# F1C100s.net
KiCad netlist of a schematic drawn in Altium Designer
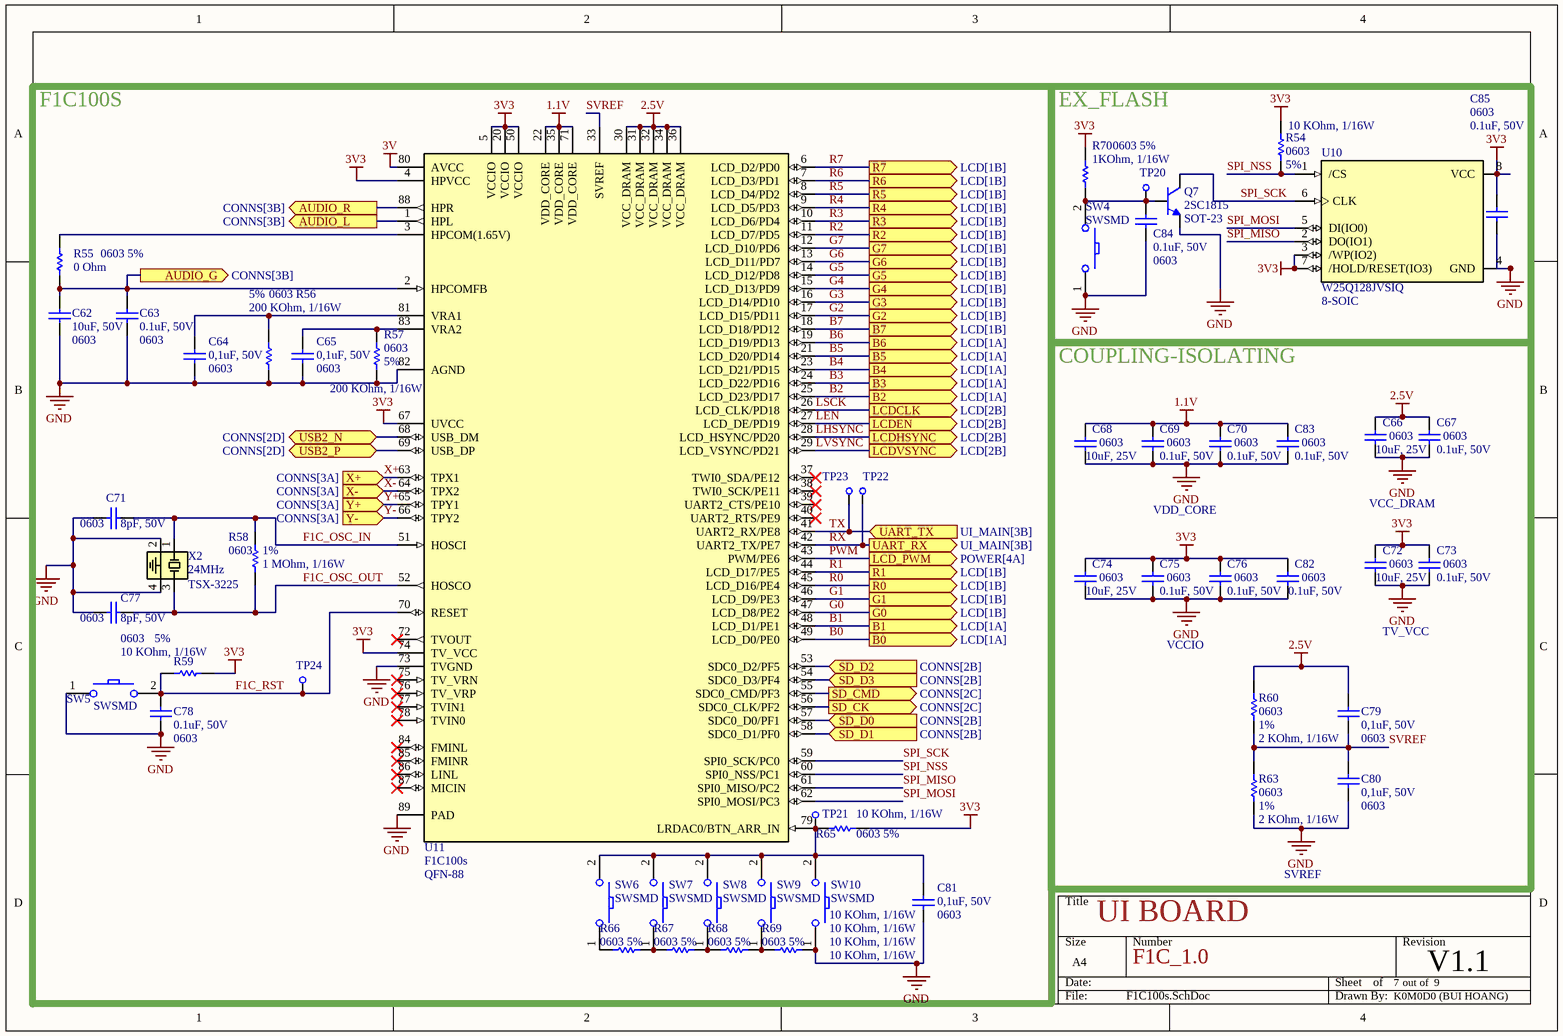
[diagram p0: F1C100s.SchDoc]

(export (version "E")
  (design (tool "Eeschema 10.0.6"))
  (components
    (comp (ref "C62")
      (value "10uF, 50V")
      (footprint "C_0603")
      (description "CAP_0603")
      (fields (field (name "PACKAGE") "0603"))
      (libsource (lib "DisplayLib") (part "CAP_0603"))
    )
    (comp (ref "C63")
      (value "0.1uF, 50V")
      (footprint "C_0603")
      (description "CAP_0603")
      (fields (field (name "PACKAGE") "0603"))
      (libsource (lib "DisplayLib") (part "CAP_0603"))
    )
    (comp (ref "C64")
      (value "0,1uF, 50V")
      (footprint "C_0603")
      (description "CAP_0603")
      (fields (field (name "PACKAGE") "0603"))
      (libsource (lib "DisplayLib") (part "CAP_0603"))
    )
    (comp (ref "C65")
      (value "0,1uF, 50V")
      (footprint "C_0603")
      (description "CAP_0603")
      (fields (field (name "PACKAGE") "0603"))
      (libsource (lib "DisplayLib") (part "CAP_0603"))
    )
    (comp (ref "C66")
      (value "10uF, 25V")
      (footprint "C_0603")
      (description "CAP_0603")
      (fields (field (name "PACKAGE") "0603"))
      (libsource (lib "DisplayLib") (part "CAP_0603"))
    )
    (comp (ref "C67")
      (value "0.1uF, 50V")
      (footprint "C_0603")
      (description "CAP_0603")
      (fields (field (name "PACKAGE") "0603"))
      (libsource (lib "DisplayLib") (part "CAP_0603"))
    )
    (comp (ref "C68")
      (value "10uF, 25V")
      (footprint "C_0603")
      (description "CAP_0603")
      (fields (field (name "PACKAGE") "0603"))
      (libsource (lib "DisplayLib") (part "CAP_0603"))
    )
    (comp (ref "C69")
      (value "0.1uF, 50V")
      (footprint "C_0603")
      (description "CAP_0603")
      (fields (field (name "PACKAGE") "0603"))
      (libsource (lib "DisplayLib") (part "CAP_0603"))
    )
    (comp (ref "C70")
      (value "0.1uF, 50V")
      (footprint "C_0603")
      (description "CAP_0603")
      (fields (field (name "PACKAGE") "0603"))
      (libsource (lib "DisplayLib") (part "CAP_0603"))
    )
    (comp (ref "C71")
      (value "8pF, 50V")
      (footprint "C_0603")
      (description "CAP_0603")
      (fields (field (name "PACKAGE") "0603"))
      (libsource (lib "DisplayLib") (part "CAP_0603"))
    )
    (comp (ref "C72")
      (value "10uF, 25V")
      (footprint "C_0603")
      (description "CAP_0603")
      (fields (field (name "PACKAGE") "0603"))
      (libsource (lib "DisplayLib") (part "CAP_0603"))
    )
    (comp (ref "C73")
      (value "0.1uF, 50V")
      (footprint "C_0603")
      (description "CAP_0603")
      (fields (field (name "PACKAGE") "0603"))
      (libsource (lib "DisplayLib") (part "CAP_0603"))
    )
    (comp (ref "C74")
      (value "10uF, 25V")
      (footprint "C_0603")
      (description "CAP_0603")
      (fields (field (name "PACKAGE") "0603"))
      (libsource (lib "DisplayLib") (part "CAP_0603"))
    )
    (comp (ref "C75")
      (value "0.1uF, 50V")
      (footprint "C_0603")
      (description "CAP_0603")
      (fields (field (name "PACKAGE") "0603"))
      (libsource (lib "DisplayLib") (part "CAP_0603"))
    )
    (comp (ref "C76")
      (value "0.1uF, 50V")
      (footprint "C_0603")
      (description "CAP_0603")
      (fields (field (name "PACKAGE") "0603"))
      (libsource (lib "DisplayLib") (part "CAP_0603"))
    )
    (comp (ref "C77")
      (value "8pF, 50V")
      (footprint "C_0603")
      (description "CAP_0603")
      (fields (field (name "PACKAGE") "0603"))
      (libsource (lib "DisplayLib") (part "CAP_0603"))
    )
    (comp (ref "C78")
      (value "0.1uF, 50V")
      (footprint "C_0603")
      (description "CAP_0603")
      (fields (field (name "PACKAGE") "0603"))
      (libsource (lib "DisplayLib") (part "CAP_0603"))
    )
    (comp (ref "C79")
      (value "0,1uF, 50V")
      (footprint "C_0603")
      (description "CAP_0603")
      (fields (field (name "PACKAGE") "0603"))
      (libsource (lib "DisplayLib") (part "CAP_0603"))
    )
    (comp (ref "C80")
      (value "0,1uF, 50V")
      (footprint "C_0603")
      (description "CAP_0603")
      (fields (field (name "PACKAGE") "0603"))
      (libsource (lib "DisplayLib") (part "CAP_0603"))
    )
    (comp (ref "C81")
      (value "0,1uF, 50V")
      (footprint "C_0603")
      (description "CAP_0603")
      (fields (field (name "PACKAGE") "0603"))
      (libsource (lib "DisplayLib") (part "CAP_0603"))
    )
    (comp (ref "C82")
      (value "0.1uF, 50V")
      (footprint "C_0603")
      (description "CAP_0603")
      (fields (field (name "PACKAGE") "0603"))
      (libsource (lib "DisplayLib") (part "CAP_0603"))
    )
    (comp (ref "C83")
      (value "0.1uF, 50V")
      (footprint "C_0603")
      (description "CAP_0603")
      (fields (field (name "PACKAGE") "0603"))
      (libsource (lib "DisplayLib") (part "CAP_0603"))
    )
    (comp (ref "C84")
      (value "0.1uF, 50V")
      (footprint "C_0603")
      (description "CAP_0603")
      (fields (field (name "PACKAGE") "0603"))
      (libsource (lib "DisplayLib") (part "CAP_0603"))
    )
    (comp (ref "C85")
      (value "0.1uF, 50V")
      (footprint "C_0603")
      (description "CAP_0603")
      (fields (field (name "PACKAGE") "0603"))
      (libsource (lib "DisplayLib") (part "CAP_0603"))
    )
    (comp (ref "Q7")
      (value "2SC1815")
      (footprint "PKG_SOT-23")
      (description "HF Transistor NPN")
      (fields (field (name "PACKAGE") "SOT-23"))
      (libsource (lib "DisplayLib") (part "2SC1815"))
    )
    (comp (ref "R54")
      (value "10 KOhm, 1/16W")
      (footprint "R_0603")
      (description "RES_0603")
      (fields (field (name "PACKAGE") "0603") (field (name "ACC") "5%"))
      (libsource (lib "DisplayLib") (part "RES_0603"))
    )
    (comp (ref "R55")
      (value "0 Ohm")
      (footprint "R_0603")
      (description "RES_0603")
      (fields (field (name "PACKAGE") "0603") (field (name "ACC") "5%"))
      (libsource (lib "DisplayLib") (part "RES_0603"))
    )
    (comp (ref "R56")
      (value "200 KOhm, 1/16W")
      (footprint "R_0603")
      (description "RES_0603")
      (fields (field (name "PACKAGE") "0603") (field (name "ACC") "5%"))
      (libsource (lib "DisplayLib") (part "RES_0603"))
    )
    (comp (ref "R57")
      (value "200 KOhm, 1/16W")
      (footprint "R_0603")
      (description "RES_0603")
      (fields (field (name "PACKAGE") "0603") (field (name "ACC") "5%"))
      (libsource (lib "DisplayLib") (part "RES_0603"))
    )
    (comp (ref "R58")
      (value "1 MOhm, 1/16W")
      (footprint "R_0603")
      (description "RES_0603")
      (fields (field (name "PACKAGE") "0603") (field (name "ACC") "1%"))
      (libsource (lib "DisplayLib") (part "RES_0603"))
    )
    (comp (ref "R59")
      (value "10 KOhm, 1/16W")
      (footprint "R_0603")
      (description "RES_0603")
      (fields (field (name "PACKAGE") "0603") (field (name "ACC") "5%"))
      (libsource (lib "DisplayLib") (part "RES_0603"))
    )
    (comp (ref "R60")
      (value "2 KOhm, 1/16W")
      (footprint "R_0603")
      (description "RES_0603")
      (fields (field (name "PACKAGE") "0603") (field (name "ACC") "1%"))
      (libsource (lib "DisplayLib") (part "RES_0603"))
    )
    (comp (ref "R63")
      (value "2 KOhm, 1/16W")
      (footprint "R_0603")
      (description "RES_0603")
      (fields (field (name "PACKAGE") "0603") (field (name "ACC") "1%"))
      (libsource (lib "DisplayLib") (part "RES_0603"))
    )
    (comp (ref "R65")
      (value "10 KOhm, 1/16W")
      (footprint "R_0603")
      (description "RES_0603")
      (fields (field (name "PACKAGE") "0603") (field (name "ACC") "5%"))
      (libsource (lib "DisplayLib") (part "RES_0603"))
    )
    (comp (ref "R66")
      (value "10 KOhm, 1/16W")
      (footprint "R_0603")
      (description "RES_0603")
      (fields (field (name "PACKAGE") "0603") (field (name "ACC") "5%"))
      (libsource (lib "DisplayLib") (part "RES_0603"))
    )
    (comp (ref "R67")
      (value "10 KOhm, 1/16W")
      (footprint "R_0603")
      (description "RES_0603")
      (fields (field (name "PACKAGE") "0603") (field (name "ACC") "5%"))
      (libsource (lib "DisplayLib") (part "RES_0603"))
    )
    (comp (ref "R68")
      (value "10 KOhm, 1/16W")
      (footprint "R_0603")
      (description "RES_0603")
      (fields (field (name "PACKAGE") "0603") (field (name "ACC") "5%"))
      (libsource (lib "DisplayLib") (part "RES_0603"))
    )
    (comp (ref "R69")
      (value "10 KOhm, 1/16W")
      (footprint "R_0603")
      (description "RES_0603")
      (fields (field (name "PACKAGE") "0603") (field (name "ACC") "5%"))
      (libsource (lib "DisplayLib") (part "RES_0603"))
    )
    (comp (ref "R70")
      (value "1KOhm, 1/16W")
      (footprint "R_0603")
      (description "RES_0603")
      (fields (field (name "PACKAGE") "0603") (field (name "ACC") "5%"))
      (libsource (lib "DisplayLib") (part "RES_0603"))
    )
    (comp (ref "SW4")
      (value "SWSMD")
      (footprint "SW_SMD_NOGND")
      (description "SW_SMD")
      (libsource (lib "") (part "SWSMD_NOGND_1"))
    )
    (comp (ref "SW5")
      (value "SWSMD")
      (footprint "SW_SMD_NOGND")
      (description "SW_SMD")
      (libsource (lib "DisplayLib") (part "SWSMD_NOGND"))
    )
    (comp (ref "SW6")
      (value "SWSMD")
      (footprint "SW_SMD_NOGND")
      (description "SW_SMD")
      (libsource (lib "") (part "SWSMD_NOGND_1"))
    )
    (comp (ref "SW7")
      (value "SWSMD")
      (footprint "SW_SMD_NOGND")
      (description "SW_SMD")
      (libsource (lib "") (part "SWSMD_NOGND_1"))
    )
    (comp (ref "SW8")
      (value "SWSMD")
      (footprint "SW_SMD_NOGND")
      (description "SW_SMD")
      (libsource (lib "") (part "SWSMD_NOGND_1"))
    )
    (comp (ref "SW9")
      (value "SWSMD")
      (footprint "SW_SMD_NOGND")
      (description "SW_SMD")
      (libsource (lib "") (part "SWSMD_NOGND_1"))
    )
    (comp (ref "SW10")
      (value "SWSMD")
      (footprint "SW_SMD_NOGND")
      (description "SW_SMD")
      (libsource (lib "") (part "SWSMD_NOGND_1"))
    )
    (comp (ref "TP20")
      (value "TESTPT")
      (footprint "TESTPT")
      (description "Test point")
      (libsource (lib "DisplayLib") (part "TESTPT"))
    )
    (comp (ref "TP21")
      (value "TESTPT")
      (footprint "TESTPT")
      (description "Test point")
      (libsource (lib "DisplayLib") (part "TESTPT"))
    )
    (comp (ref "TP22")
      (value "TESTPT")
      (footprint "TESTPT")
      (description "Test point")
      (libsource (lib "DisplayLib") (part "TESTPT"))
    )
    (comp (ref "TP23")
      (value "TESTPT")
      (footprint "TESTPT")
      (description "Test point")
      (libsource (lib "DisplayLib") (part "TESTPT"))
    )
    (comp (ref "TP24")
      (value "TESTPT")
      (footprint "TESTPT")
      (description "Test point")
      (libsource (lib "DisplayLib") (part "TESTPT"))
    )
    (comp (ref "U10")
      (value "W25Q128JVSIQ")
      (footprint "PKG_8-SOIC")
      (description "FLASH - NOR Memory IC 128Mb (16M x 8) SPI - Quad I/O, QPI, DTR 133 MHz 8-SOIC")
      (fields (field (name "PACKAGE") "8-SOIC"))
      (libsource (lib "DisplayLib") (part "W25Q128JVSIQ"))
    )
    (comp (ref "U11")
      (value "F1C100s")
      (footprint "PKG_QFN-88")
      (fields (field (name "PACKAGE") "QFN-88"))
      (libsource (lib "DisplayLib") (part "F1C100s"))
    )
    (comp (ref "X2")
      (value "24MHz")
      (footprint "PKG_TSX-3225")
      (description "Crystal, 24 MHz, -30 to 85 degC, 3.2 x 2.5 x 0.9 mm SMD")
      (fields (field (name "PACKAGE") "TSX-3225"))
      (libsource (lib "DisplayLib") (part "XTAL"))
    )
  )
  (nets
    (net (code "1") (name "/AUDIO_G") (class "Default")
      (node (ref "C62") (pin "2") (pinfunction "2_2") (pintype "passive"))
      (node (ref "C63") (pin "2") (pinfunction "2_2") (pintype "passive"))
      (node (ref "R55") (pin "1") (pinfunction "1_1") (pintype "passive"))
      (node (ref "U11") (pin "2") (pinfunction "HPCOMFB_2") (pintype "input"))
    )
    (net (code "2") (name "/AUDIO_L") (class "Default")
      (node (ref "U11") (pin "1") (pinfunction "HPL_1") (pintype "output"))
    )
    (net (code "3") (name "/AUDIO_R") (class "Default")
      (node (ref "U11") (pin "88") (pinfunction "HPR_88") (pintype "output"))
    )
    (net (code "4") (name "/B0") (class "Default")
      (node (ref "U11") (pin "49") (pinfunction "LCD_D0/PE0_49") (pintype "bidirectional"))
    )
    (net (code "5") (name "/B1") (class "Default")
      (node (ref "U11") (pin "48") (pinfunction "LCD_D1/PE1_48") (pintype "bidirectional"))
    )
    (net (code "6") (name "/B2") (class "Default")
      (node (ref "U11") (pin "25") (pinfunction "LCD_D23/PD17_25") (pintype "bidirectional"))
    )
    (net (code "7") (name "/B3") (class "Default")
      (node (ref "U11") (pin "24") (pinfunction "LCD_D22/PD16_24") (pintype "bidirectional"))
    )
    (net (code "8") (name "/B4") (class "Default")
      (node (ref "U11") (pin "23") (pinfunction "LCD_D21/PD15_23") (pintype "bidirectional"))
    )
    (net (code "9") (name "/B5") (class "Default")
      (node (ref "U11") (pin "21") (pinfunction "LCD_D20/PD14_21") (pintype "bidirectional"))
    )
    (net (code "10") (name "/B6") (class "Default")
      (node (ref "U11") (pin "19") (pinfunction "LCD_D19/PD13_19") (pintype "bidirectional"))
    )
    (net (code "11") (name "/B7") (class "Default")
      (node (ref "U11") (pin "18") (pinfunction "LCD_D18/PD12_18") (pintype "bidirectional"))
    )
    (net (code "12") (name "/F1C_OSC_IN") (class "Default")
      (node (ref "C71") (pin "2") (pinfunction "2_2") (pintype "passive"))
      (node (ref "R58") (pin "2") (pinfunction "2_2") (pintype "passive"))
      (node (ref "U11") (pin "51") (pinfunction "HOSCI_51") (pintype "input"))
      (node (ref "X2") (pin "1") (pinfunction "1_1") (pintype "passive"))
    )
    (net (code "13") (name "/F1C_OSC_OUT") (class "Default")
      (node (ref "C77") (pin "2") (pinfunction "2_2") (pintype "passive"))
      (node (ref "R58") (pin "1") (pinfunction "1_1") (pintype "passive"))
      (node (ref "U11") (pin "52") (pinfunction "HOSCO_52") (pintype "output"))
      (node (ref "X2") (pin "3") (pinfunction "3_3") (pintype "passive"))
    )
    (net (code "14") (name "/F1C_RST") (class "Default")
      (node (ref "C78") (pin "2") (pinfunction "2_2") (pintype "passive"))
      (node (ref "R59") (pin "1") (pinfunction "1_1") (pintype "passive"))
      (node (ref "SW5") (pin "2") (pinfunction "2_2") (pintype "passive"))
      (node (ref "TP24") (pin "1") (pinfunction "1_1") (pintype "passive"))
      (node (ref "U11") (pin "70") (pinfunction "RESET_70") (pintype "bidirectional"))
    )
    (net (code "15") (name "/G0") (class "Default")
      (node (ref "U11") (pin "47") (pinfunction "LCD_D8/PE2_47") (pintype "bidirectional"))
    )
    (net (code "16") (name "/G1") (class "Default")
      (node (ref "U11") (pin "46") (pinfunction "LCD_D9/PE3_46") (pintype "bidirectional"))
    )
    (net (code "17") (name "/G2") (class "Default")
      (node (ref "U11") (pin "17") (pinfunction "LCD_D15/PD11_17") (pintype "bidirectional"))
    )
    (net (code "18") (name "/G3") (class "Default")
      (node (ref "U11") (pin "16") (pinfunction "LCD_D14/PD10_16") (pintype "bidirectional"))
    )
    (net (code "19") (name "/G4") (class "Default")
      (node (ref "U11") (pin "15") (pinfunction "LCD_D13/PD9_15") (pintype "bidirectional"))
    )
    (net (code "20") (name "/G5") (class "Default")
      (node (ref "U11") (pin "14") (pinfunction "LCD_D12/PD8_14") (pintype "bidirectional"))
    )
    (net (code "21") (name "/G6") (class "Default")
      (node (ref "U11") (pin "13") (pinfunction "LCD_D11/PD7_13") (pintype "bidirectional"))
    )
    (net (code "22") (name "/G7") (class "Default")
      (node (ref "U11") (pin "12") (pinfunction "LCD_D10/PD6_12") (pintype "bidirectional"))
    )
    (net (code "23") (name "/LEN") (class "Default")
      (node (ref "U11") (pin "27") (pinfunction "LCD_DE/PD19_27") (pintype "bidirectional"))
    )
    (net (code "24") (name "/LHSYNC") (class "Default")
      (node (ref "U11") (pin "28") (pinfunction "LCD_HSYNC/PD20_28") (pintype "bidirectional"))
    )
    (net (code "25") (name "/LSCK") (class "Default")
      (node (ref "U11") (pin "26") (pinfunction "LCD_CLK/PD18_26") (pintype "bidirectional"))
    )
    (net (code "26") (name "/LVSYNC") (class "Default")
      (node (ref "U11") (pin "29") (pinfunction "LCD_VSYNC/PD21_29") (pintype "bidirectional"))
    )
    (net (code "27") (name "/PWM") (class "Default")
      (node (ref "U11") (pin "43") (pinfunction "PWM/PE6_43") (pintype "bidirectional"))
    )
    (net (code "28") (name "/R0") (class "Default")
      (node (ref "U11") (pin "45") (pinfunction "LCD_D16/PE4_45") (pintype "bidirectional"))
    )
    (net (code "29") (name "/R1") (class "Default")
      (node (ref "U11") (pin "44") (pinfunction "LCD_D17/PE5_44") (pintype "bidirectional"))
    )
    (net (code "30") (name "/R2") (class "Default")
      (node (ref "U11") (pin "11") (pinfunction "LCD_D7/PD5_11") (pintype "bidirectional"))
    )
    (net (code "31") (name "/R3") (class "Default")
      (node (ref "U11") (pin "10") (pinfunction "LCD_D6/PD4_10") (pintype "bidirectional"))
    )
    (net (code "32") (name "/R4") (class "Default")
      (node (ref "U11") (pin "9") (pinfunction "LCD_D5/PD3_9") (pintype "bidirectional"))
    )
    (net (code "33") (name "/R5") (class "Default")
      (node (ref "U11") (pin "8") (pinfunction "LCD_D4/PD2_8") (pintype "bidirectional"))
    )
    (net (code "34") (name "/R6") (class "Default")
      (node (ref "U11") (pin "7") (pinfunction "LCD_D3/PD1_7") (pintype "bidirectional"))
    )
    (net (code "35") (name "/R7") (class "Default")
      (node (ref "U11") (pin "6") (pinfunction "LCD_D2/PD0_6") (pintype "bidirectional"))
    )
    (net (code "36") (name "/RX") (class "Default")
      (node (ref "TP22") (pin "1") (pinfunction "1_1") (pintype "passive"))
      (node (ref "U11") (pin "42") (pinfunction "UART2_TX/PE7_42") (pintype "bidirectional"))
    )
    (net (code "37") (name "/SD_CK") (class "Default")
      (node (ref "U11") (pin "56") (pinfunction "SDC0_CLK/PF2_56") (pintype "bidirectional"))
    )
    (net (code "38") (name "/SD_CMD") (class "Default")
      (node (ref "U11") (pin "55") (pinfunction "SDC0_CMD/PF3_55") (pintype "bidirectional"))
    )
    (net (code "39") (name "/SD_D0") (class "Default")
      (node (ref "U11") (pin "57") (pinfunction "SDC0_D0/PF1_57") (pintype "bidirectional"))
    )
    (net (code "40") (name "/SD_D1") (class "Default")
      (node (ref "U11") (pin "58") (pinfunction "SDC0_D1/PF0_58") (pintype "bidirectional"))
    )
    (net (code "41") (name "/SD_D2") (class "Default")
      (node (ref "U11") (pin "53") (pinfunction "SDC0_D2/PF5_53") (pintype "bidirectional"))
    )
    (net (code "42") (name "/SD_D3") (class "Default")
      (node (ref "U11") (pin "54") (pinfunction "SDC0_D3/PF4_54") (pintype "bidirectional"))
    )
    (net (code "43") (name "/SPI_MISO") (class "Default")
      (node (ref "U10") (pin "2") (pinfunction "DO(IO1)_2") (pintype "bidirectional"))
      (node (ref "U11") (pin "61") (pinfunction "SPI0_MISO/PC2_61") (pintype "bidirectional"))
    )
    (net (code "44") (name "/SPI_MOSI") (class "Default")
      (node (ref "U10") (pin "5") (pinfunction "DI(IO0)_5") (pintype "bidirectional"))
      (node (ref "U11") (pin "62") (pinfunction "SPI0_MOSI/PC3_62") (pintype "bidirectional"))
    )
    (net (code "45") (name "/SPI_NSS") (class "Default")
      (node (ref "R54") (pin "1") (pinfunction "1_1") (pintype "passive"))
      (node (ref "U10") (pin "1") (pinfunction "/CS_1") (pintype "input"))
      (node (ref "U11") (pin "60") (pinfunction "SPI0_NSS/PC1_60") (pintype "bidirectional"))
    )
    (net (code "46") (name "/SPI_SCK") (class "Default")
      (node (ref "Q7") (pin "3") (pinfunction "C_3") (pintype "passive"))
      (node (ref "U10") (pin "6") (pinfunction "CLK_6") (pintype "input"))
      (node (ref "U11") (pin "59") (pinfunction "SPI0_SCK/PC0_59") (pintype "bidirectional"))
    )
    (net (code "47") (name "/SVREF") (class "Default")
      (node (ref "C79") (pin "1") (pinfunction "1_1") (pintype "passive"))
      (node (ref "C80") (pin "2") (pinfunction "2_2") (pintype "passive"))
      (node (ref "R60") (pin "1") (pinfunction "1_1") (pintype "passive"))
      (node (ref "R63") (pin "2") (pinfunction "2_2") (pintype "passive"))
      (node (ref "U11") (pin "33") (pinfunction "SVREF_33") (pintype "power_in"))
    )
    (net (code "48") (name "/TX") (class "Default")
      (node (ref "TP23") (pin "1") (pinfunction "1_1") (pintype "passive"))
      (node (ref "U11") (pin "41") (pinfunction "UART2_RX/PE8_41") (pintype "bidirectional"))
    )
    (net (code "49") (name "/USB2_N") (class "Default")
      (node (ref "U11") (pin "68") (pinfunction "USB_DM_68") (pintype "bidirectional"))
    )
    (net (code "50") (name "/USB2_P") (class "Default")
      (node (ref "U11") (pin "69") (pinfunction "USB_DP_69") (pintype "bidirectional"))
    )
    (net (code "51") (name "/X+") (class "Default")
      (node (ref "U11") (pin "63") (pinfunction "TPX1_63") (pintype "bidirectional"))
    )
    (net (code "52") (name "/X-") (class "Default")
      (node (ref "U11") (pin "64") (pinfunction "TPX2_64") (pintype "bidirectional"))
    )
    (net (code "53") (name "/Y+") (class "Default")
      (node (ref "U11") (pin "65") (pinfunction "TPY1_65") (pintype "bidirectional"))
    )
    (net (code "54") (name "/Y-") (class "Default")
      (node (ref "U11") (pin "66") (pinfunction "TPY2_66") (pintype "bidirectional"))
    )
    (net (code "55") (name "1.1V") (class "Default")
      (node (ref "C68") (pin "2") (pinfunction "2_2") (pintype "passive"))
      (node (ref "C69") (pin "2") (pinfunction "2_2") (pintype "passive"))
      (node (ref "C70") (pin "2") (pinfunction "2_2") (pintype "passive"))
      (node (ref "C83") (pin "2") (pinfunction "2_2") (pintype "passive"))
      (node (ref "U11") (pin "22") (pinfunction "VDD_CORE_22") (pintype "power_in"))
      (node (ref "U11") (pin "35") (pinfunction "VDD_CORE_35") (pintype "power_in"))
      (node (ref "U11") (pin "71") (pinfunction "VDD_CORE_71") (pintype "power_in"))
    )
    (net (code "56") (name "2.5V") (class "Default")
      (node (ref "C66") (pin "2") (pinfunction "2_2") (pintype "passive"))
      (node (ref "C67") (pin "2") (pinfunction "2_2") (pintype "passive"))
      (node (ref "C79") (pin "2") (pinfunction "2_2") (pintype "passive"))
      (node (ref "R60") (pin "2") (pinfunction "2_2") (pintype "passive"))
      (node (ref "U11") (pin "30") (pinfunction "VCC_DRAM_30") (pintype "power_in"))
      (node (ref "U11") (pin "31") (pinfunction "VCC_DRAM_31") (pintype "power_in"))
      (node (ref "U11") (pin "32") (pinfunction "VCC_DRAM_32") (pintype "power_in"))
      (node (ref "U11") (pin "34") (pinfunction "VCC_DRAM_34") (pintype "power_in"))
      (node (ref "U11") (pin "36") (pinfunction "VCC_DRAM_36") (pintype "power_in"))
    )
    (net (code "57") (name "3V") (class "Default")
      (node (ref "U11") (pin "80") (pinfunction "AVCC_80") (pintype "power_in"))
    )
    (net (code "58") (name "3V3") (class "Default")
      (node (ref "C72") (pin "2") (pinfunction "2_2") (pintype "passive"))
      (node (ref "C73") (pin "2") (pinfunction "2_2") (pintype "passive"))
      (node (ref "C74") (pin "2") (pinfunction "2_2") (pintype "passive"))
      (node (ref "C75") (pin "2") (pinfunction "2_2") (pintype "passive"))
      (node (ref "C76") (pin "2") (pinfunction "2_2") (pintype "passive"))
      (node (ref "C82") (pin "2") (pinfunction "2_2") (pintype "passive"))
      (node (ref "C85") (pin "2") (pinfunction "2_2") (pintype "passive"))
      (node (ref "R54") (pin "2") (pinfunction "2_2") (pintype "passive"))
      (node (ref "R59") (pin "2") (pinfunction "2_2") (pintype "passive"))
      (node (ref "R65") (pin "2") (pinfunction "2_2") (pintype "passive"))
      (node (ref "R70") (pin "2") (pinfunction "2_2") (pintype "passive"))
      (node (ref "U10") (pin "3") (pinfunction "/WP(IO2)_3") (pintype "bidirectional"))
      (node (ref "U10") (pin "7") (pinfunction "/HOLD/RESET(IO3)_7") (pintype "bidirectional"))
      (node (ref "U10") (pin "8") (pinfunction "VCC_8") (pintype "power_in"))
      (node (ref "U11") (pin "20") (pinfunction "VCCIO_20") (pintype "power_in"))
      (node (ref "U11") (pin "4") (pinfunction "HPVCC_4") (pintype "power_in"))
      (node (ref "U11") (pin "5") (pinfunction "VCCIO_5") (pintype "power_in"))
      (node (ref "U11") (pin "50") (pinfunction "VCCIO_50") (pintype "power_in"))
      (node (ref "U11") (pin "67") (pinfunction "UVCC_67") (pintype "power_in"))
      (node (ref "U11") (pin "74") (pinfunction "TV_VCC_74") (pintype "power_in"))
    )
    (net (code "59") (name "GND") (class "Default")
      (node (ref "C62") (pin "1") (pinfunction "1_1") (pintype "passive"))
      (node (ref "C63") (pin "1") (pinfunction "1_1") (pintype "passive"))
      (node (ref "C64") (pin "1") (pinfunction "1_1") (pintype "passive"))
      (node (ref "C65") (pin "1") (pinfunction "1_1") (pintype "passive"))
      (node (ref "C66") (pin "1") (pinfunction "1_1") (pintype "passive"))
      (node (ref "C67") (pin "1") (pinfunction "1_1") (pintype "passive"))
      (node (ref "C68") (pin "1") (pinfunction "1_1") (pintype "passive"))
      (node (ref "C69") (pin "1") (pinfunction "1_1") (pintype "passive"))
      (node (ref "C70") (pin "1") (pinfunction "1_1") (pintype "passive"))
      (node (ref "C71") (pin "1") (pinfunction "1_1") (pintype "passive"))
      (node (ref "C72") (pin "1") (pinfunction "1_1") (pintype "passive"))
      (node (ref "C73") (pin "1") (pinfunction "1_1") (pintype "passive"))
      (node (ref "C74") (pin "1") (pinfunction "1_1") (pintype "passive"))
      (node (ref "C75") (pin "1") (pinfunction "1_1") (pintype "passive"))
      (node (ref "C76") (pin "1") (pinfunction "1_1") (pintype "passive"))
      (node (ref "C77") (pin "1") (pinfunction "1_1") (pintype "passive"))
      (node (ref "C78") (pin "1") (pinfunction "1_1") (pintype "passive"))
      (node (ref "C80") (pin "1") (pinfunction "1_1") (pintype "passive"))
      (node (ref "C81") (pin "1") (pinfunction "1_1") (pintype "passive"))
      (node (ref "C82") (pin "1") (pinfunction "1_1") (pintype "passive"))
      (node (ref "C83") (pin "1") (pinfunction "1_1") (pintype "passive"))
      (node (ref "C84") (pin "1") (pinfunction "1_1") (pintype "passive"))
      (node (ref "C85") (pin "1") (pinfunction "1_1") (pintype "passive"))
      (node (ref "Q7") (pin "2") (pinfunction "E_2") (pintype "passive"))
      (node (ref "R56") (pin "1") (pinfunction "1_1") (pintype "passive"))
      (node (ref "R57") (pin "1") (pinfunction "1_1") (pintype "passive"))
      (node (ref "R63") (pin "1") (pinfunction "1_1") (pintype "passive"))
      (node (ref "R69") (pin "2") (pinfunction "2_2") (pintype "passive"))
      (node (ref "SW10") (pin "1") (pinfunction "1_1") (pintype "passive"))
      (node (ref "SW4") (pin "1") (pinfunction "1_1") (pintype "passive"))
      (node (ref "SW5") (pin "1") (pinfunction "1_1") (pintype "passive"))
      (node (ref "U10") (pin "4") (pinfunction "GND_4") (pintype "power_in"))
      (node (ref "U11") (pin "73") (pinfunction "TVGND_73") (pintype "power_in"))
      (node (ref "U11") (pin "82") (pinfunction "AGND_82") (pintype "power_in"))
      (node (ref "U11") (pin "89") (pinfunction "PAD_89") (pintype "passive"))
      (node (ref "X2") (pin "2") (pinfunction "2_2") (pintype "passive"))
      (node (ref "X2") (pin "4") (pinfunction "4_4") (pintype "passive"))
    )
    (net (code "60") (name "Net-(Q7-B)") (class "Default")
      (node (ref "C84") (pin "2") (pinfunction "2_2") (pintype "passive"))
      (node (ref "Q7") (pin "1") (pinfunction "B_1") (pintype "passive"))
      (node (ref "R70") (pin "1") (pinfunction "1_1") (pintype "passive"))
      (node (ref "SW4") (pin "2") (pinfunction "2_2") (pintype "passive"))
      (node (ref "TP20") (pin "1") (pinfunction "1_1") (pintype "passive"))
    )
    (net (code "61") (name "Net-(R66-Pad1)") (class "Default")
      (node (ref "R66") (pin "1") (pinfunction "1_1") (pintype "passive"))
      (node (ref "SW6") (pin "1") (pinfunction "1_1") (pintype "passive"))
    )
    (net (code "62") (name "Net-(R66-Pad2)") (class "Default")
      (node (ref "R66") (pin "2") (pinfunction "2_2") (pintype "passive"))
      (node (ref "R67") (pin "1") (pinfunction "1_1") (pintype "passive"))
      (node (ref "SW7") (pin "1") (pinfunction "1_1") (pintype "passive"))
    )
    (net (code "63") (name "Net-(R67-Pad2)") (class "Default")
      (node (ref "R67") (pin "2") (pinfunction "2_2") (pintype "passive"))
      (node (ref "R68") (pin "1") (pinfunction "1_1") (pintype "passive"))
      (node (ref "SW8") (pin "1") (pinfunction "1_1") (pintype "passive"))
    )
    (net (code "64") (name "Net-(R68-Pad2)") (class "Default")
      (node (ref "R68") (pin "2") (pinfunction "2_2") (pintype "passive"))
      (node (ref "R69") (pin "1") (pinfunction "1_1") (pintype "passive"))
      (node (ref "SW9") (pin "1") (pinfunction "1_1") (pintype "passive"))
    )
    (net (code "65") (name "Net-(U11-HPCOM(1.65V))") (class "Default")
      (node (ref "R55") (pin "2") (pinfunction "2_2") (pintype "passive"))
      (node (ref "U11") (pin "3") (pinfunction "HPCOM(1.65V)_3") (pintype "power_in"))
    )
    (net (code "66") (name "Net-(U11-LRDAC0{slash}BTN_ARR_IN)") (class "Default")
      (node (ref "C81") (pin "2") (pinfunction "2_2") (pintype "passive"))
      (node (ref "R65") (pin "1") (pinfunction "1_1") (pintype "passive"))
      (node (ref "SW10") (pin "2") (pinfunction "2_2") (pintype "passive"))
      (node (ref "SW6") (pin "2") (pinfunction "2_2") (pintype "passive"))
      (node (ref "SW7") (pin "2") (pinfunction "2_2") (pintype "passive"))
      (node (ref "SW8") (pin "2") (pinfunction "2_2") (pintype "passive"))
      (node (ref "SW9") (pin "2") (pinfunction "2_2") (pintype "passive"))
      (node (ref "TP21") (pin "1") (pinfunction "1_1") (pintype "passive"))
      (node (ref "U11") (pin "79") (pinfunction "LRDAC0/BTN_ARR_IN_79") (pintype "input"))
    )
    (net (code "67") (name "Net-(U11-VRA1)") (class "Default")
      (node (ref "C64") (pin "2") (pinfunction "2_2") (pintype "passive"))
      (node (ref "R56") (pin "2") (pinfunction "2_2") (pintype "passive"))
      (node (ref "U11") (pin "81") (pinfunction "VRA1_81") (pintype "passive"))
    )
    (net (code "68") (name "Net-(U11-VRA2)") (class "Default")
      (node (ref "C65") (pin "2") (pinfunction "2_2") (pintype "passive"))
      (node (ref "R57") (pin "2") (pinfunction "2_2") (pintype "passive"))
      (node (ref "U11") (pin "83") (pinfunction "VRA2_83") (pintype "passive"))
    )
    (net (code "69") (name "unconnected-(U11-FMINL-Pad84)") (class "Default")
      (node (ref "U11") (pin "84") (pinfunction "FMINL_84") (pintype "bidirectional+no_connect"))
    )
    (net (code "70") (name "unconnected-(U11-FMINR-Pad85)") (class "Default")
      (node (ref "U11") (pin "85") (pinfunction "FMINR_85") (pintype "bidirectional+no_connect"))
    )
    (net (code "71") (name "unconnected-(U11-LINL-Pad86)") (class "Default")
      (node (ref "U11") (pin "86") (pinfunction "LINL_86") (pintype "bidirectional+no_connect"))
    )
    (net (code "72") (name "unconnected-(U11-MICIN-Pad87)") (class "Default")
      (node (ref "U11") (pin "87") (pinfunction "MICIN_87") (pintype "bidirectional+no_connect"))
    )
    (net (code "73") (name "unconnected-(U11-TVIN0-Pad78)") (class "Default")
      (node (ref "U11") (pin "78") (pinfunction "TVIN0_78") (pintype "input+no_connect"))
    )
    (net (code "74") (name "unconnected-(U11-TVIN1-Pad77)") (class "Default")
      (node (ref "U11") (pin "77") (pinfunction "TVIN1_77") (pintype "input+no_connect"))
    )
    (net (code "75") (name "unconnected-(U11-TVOUT-Pad72)") (class "Default")
      (node (ref "U11") (pin "72") (pinfunction "TVOUT_72") (pintype "output+no_connect"))
    )
    (net (code "76") (name "unconnected-(U11-TV_VRN-Pad75)") (class "Default")
      (node (ref "U11") (pin "75") (pinfunction "TV_VRN_75") (pintype "input+no_connect"))
    )
    (net (code "77") (name "unconnected-(U11-TV_VRP-Pad76)") (class "Default")
      (node (ref "U11") (pin "76") (pinfunction "TV_VRP_76") (pintype "input+no_connect"))
    )
    (net (code "78") (name "unconnected-(U11-TWI0_SCK{slash}PE11-Pad38)") (class "Default")
      (node (ref "U11") (pin "38") (pinfunction "TWI0_SCK/PE11_38") (pintype "bidirectional+no_connect"))
    )
    (net (code "79") (name "unconnected-(U11-TWI0_SDA{slash}PE12-Pad37)") (class "Default")
      (node (ref "U11") (pin "37") (pinfunction "TWI0_SDA/PE12_37") (pintype "bidirectional+no_connect"))
    )
    (net (code "80") (name "unconnected-(U11-UART2_CTS{slash}PE10-Pad39)") (class "Default")
      (node (ref "U11") (pin "39") (pinfunction "UART2_CTS/PE10_39") (pintype "bidirectional+no_connect"))
    )
    (net (code "81") (name "unconnected-(U11-UART2_RTS{slash}PE9-Pad40)") (class "Default")
      (node (ref "U11") (pin "40") (pinfunction "UART2_RTS/PE9_40") (pintype "bidirectional+no_connect"))
    )
  )
)
